# surficial_tilt_shield.net
KiCad netlist of a schematic drawn in EAGLE
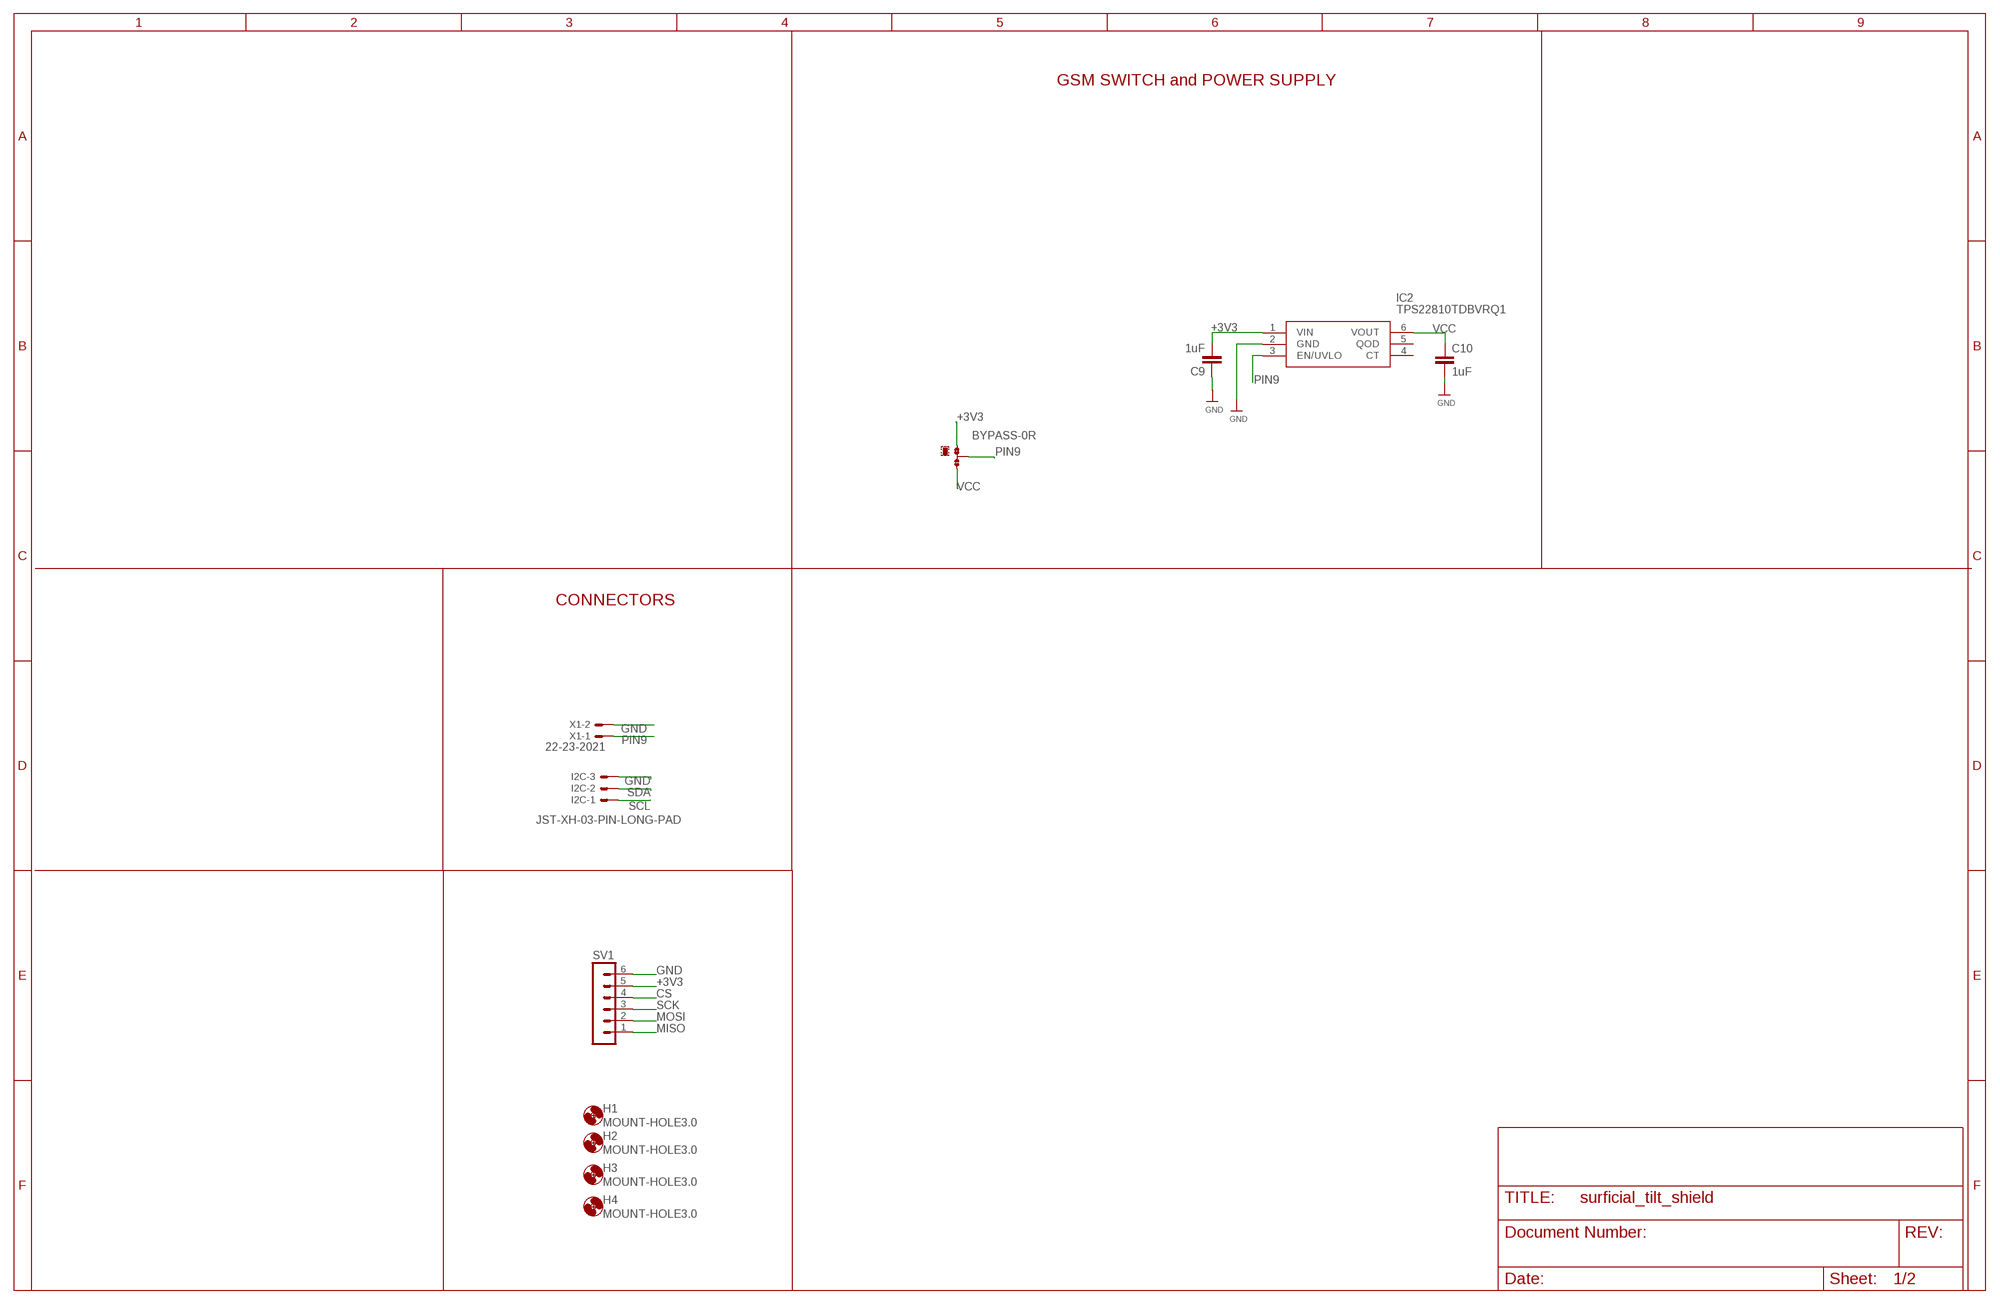
[diagram p0: schematic, sheet 1]
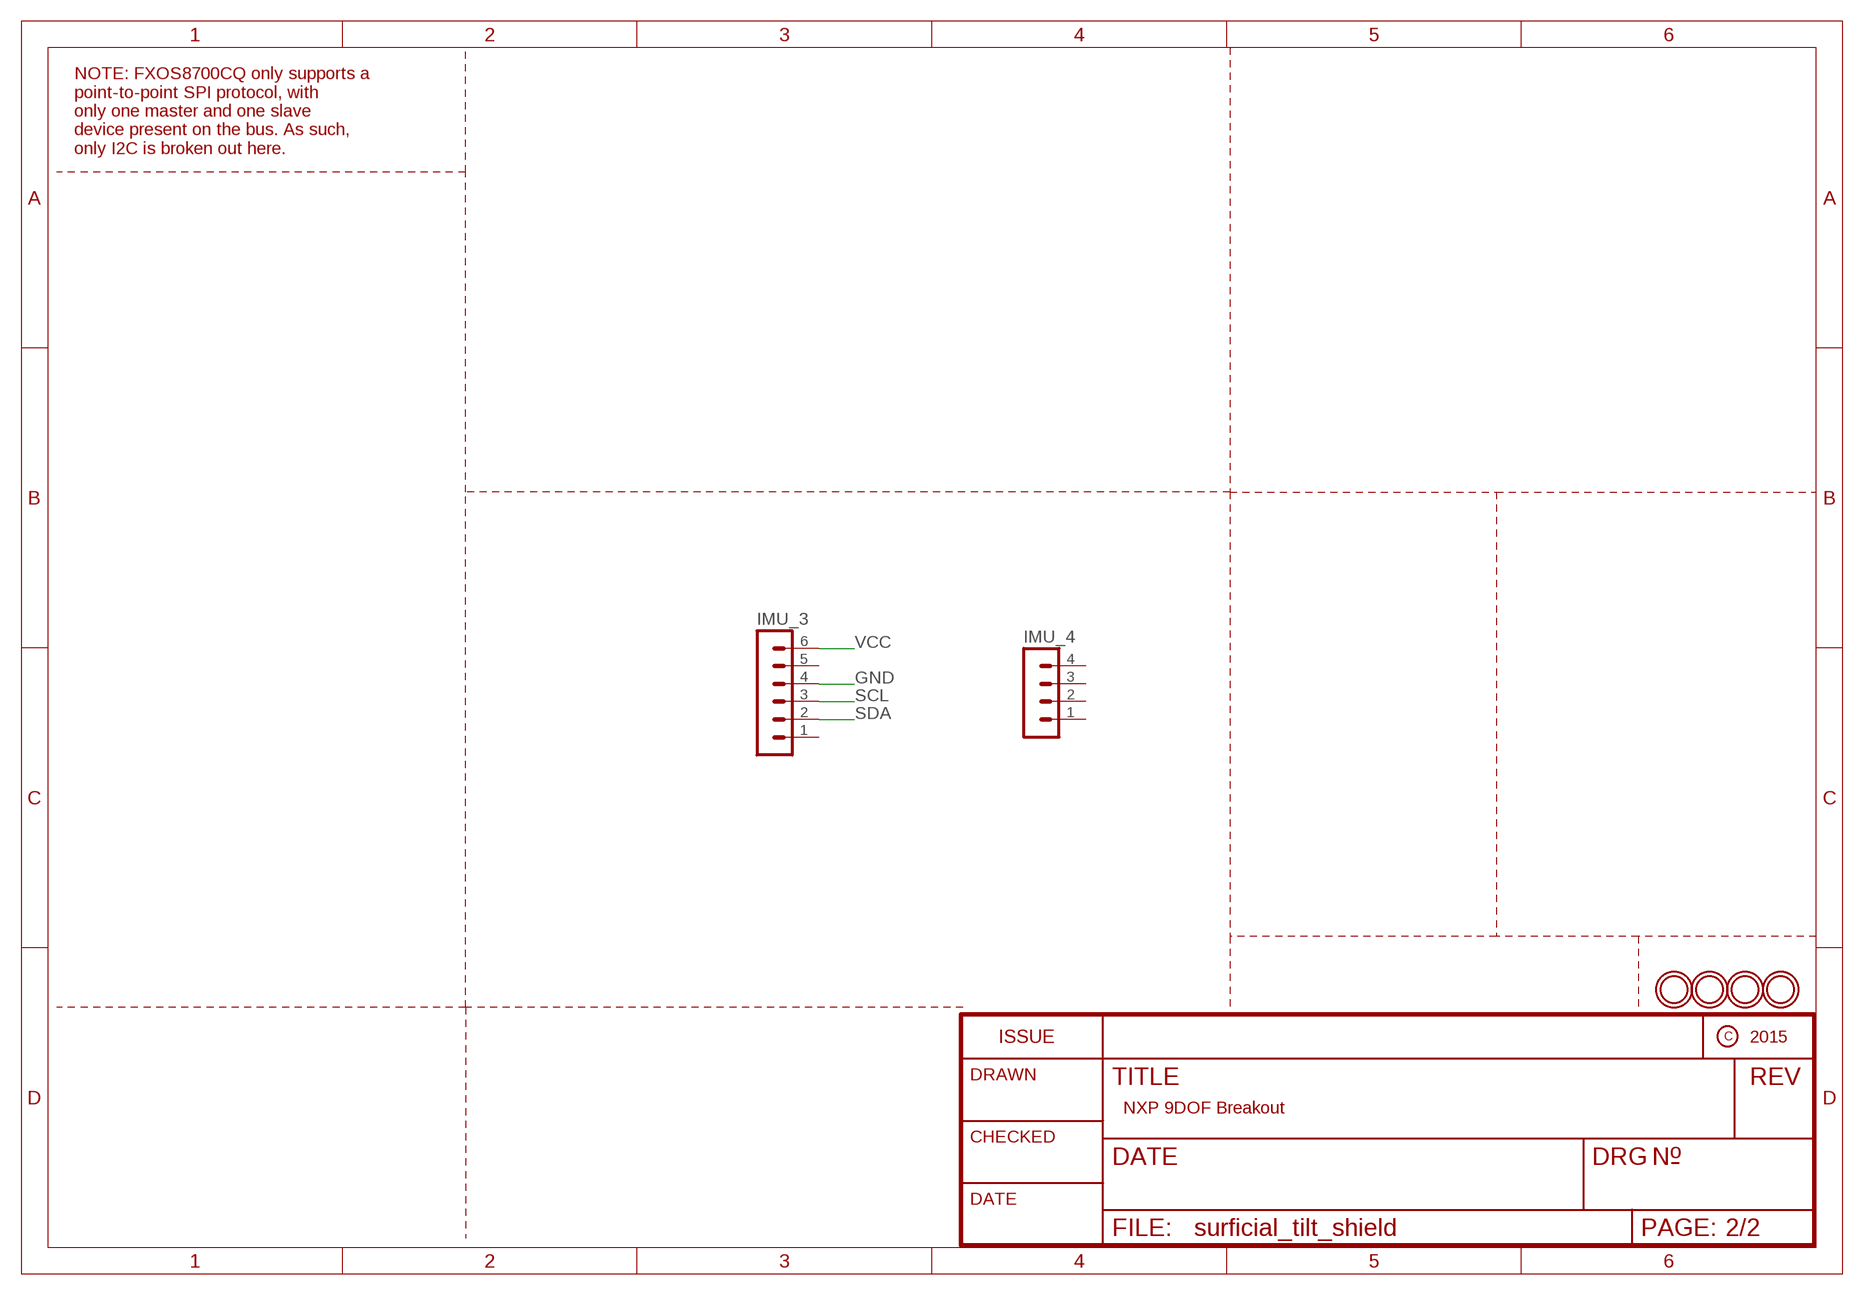
[diagram p1: schematic, sheet 2]

(export (version "E")
  (design (tool "Eeschema 10.0.6"))
  (components
    (comp (ref "BYPASS")
      (value "0R-JUMPB")
      (footprint "eagle-import:B0R-JMP")
      (libsource (lib "eagle-import") (part "0R-JUMPB"))
    )
    (comp (ref "C9")
      (value "1uF")
      (footprint "eagle-import:C0603")
      (libsource (lib "eagle-import") (part "CC0603"))
    )
    (comp (ref "C10")
      (value "1uF")
      (footprint "eagle-import:C0603")
      (libsource (lib "eagle-import") (part "CC0603"))
    )
    (comp (ref "H1")
      (value "MOUNT-HOLE3.0")
      (footprint "eagle-import:3,0")
      (libsource (lib "eagle-import") (part "MOUNT-HOLE3.0"))
    )
    (comp (ref "H2")
      (value "MOUNT-HOLE3.0")
      (footprint "eagle-import:3,0")
      (libsource (lib "eagle-import") (part "MOUNT-HOLE3.0"))
    )
    (comp (ref "H3")
      (value "MOUNT-HOLE3.0")
      (footprint "eagle-import:3,0")
      (libsource (lib "eagle-import") (part "MOUNT-HOLE3.0"))
    )
    (comp (ref "H4")
      (value "MOUNT-HOLE3.0")
      (footprint "eagle-import:3,0")
      (libsource (lib "eagle-import") (part "MOUNT-HOLE3.0"))
    )
    (comp (ref "I2C")
      (value "JST-XH-03-PIN-LONG-PAD")
      (footprint "eagle-import:JST-XH-03-PACKAGE-LONG-PAD")
      (libsource (lib "eagle-import") (part "JST-XH-03-PIN-LONG-PAD"))
    )
    (comp (ref "IC2")
      (value "TPS22810TDBVRQ1")
      (footprint "eagle-import:SOT95P280X145-6N")
      (libsource (lib "eagle-import") (part "TPS22810TDBVRQ1"))
    )
    (comp (ref "SV1")
      (value "MA06-1")
      (footprint "eagle-import:MA06-1")
      (libsource (lib "eagle-import") (part "MA06-1"))
    )
    (comp (ref "X1")
      (value "22-23-2021")
      (footprint "eagle-import:22-23-2021")
      (fields (field (name "MF") "MOLEX"))
      (libsource (lib "eagle-import") (part "22-23-2021"))
    )
    (comp (ref "IMU_3")
      (value "MA06-1")
      (footprint "eagle-import:MA06-1")
      (libsource (lib "eagle-import") (part "MA06-1"))
    )
    (comp (ref "IMU_4")
      (value "MA04-1")
      (footprint "eagle-import:MA04-1")
      (libsource (lib "eagle-import") (part "MA04-1"))
    )
    (comp (ref "U$1")
      (value "MOUNTINGHOLE2.5")
      (footprint "eagle-import:MOUNTINGHOLE_2.5_PLATED")
      (libsource (lib "eagle-import") (part "MOUNTINGHOLE2.5"))
    )
    (comp (ref "U$2")
      (value "MOUNTINGHOLE2.5")
      (footprint "eagle-import:MOUNTINGHOLE_2.5_PLATED")
      (libsource (lib "eagle-import") (part "MOUNTINGHOLE2.5"))
    )
    (comp (ref "U$3")
      (value "MOUNTINGHOLE2.5")
      (footprint "eagle-import:MOUNTINGHOLE_2.5_PLATED")
      (libsource (lib "eagle-import") (part "MOUNTINGHOLE2.5"))
    )
    (comp (ref "U$4")
      (value "MOUNTINGHOLE2.5")
      (footprint "eagle-import:MOUNTINGHOLE_2.5_PLATED")
      (libsource (lib "eagle-import") (part "MOUNTINGHOLE2.5"))
    )
  )
  (nets
    (net (code "1") (name "+3V3") (class "Default")
      (node (ref "BYPASS") (pin "1") (pinfunction "1_1") (pintype "passive"))
      (node (ref "C9") (pin "2") (pinfunction "2_2") (pintype "passive"))
      (node (ref "IC2") (pin "1") (pinfunction "VIN_1") (pintype "bidirectional"))
      (node (ref "SV1") (pin "5") (pinfunction "5_5") (pintype "passive"))
    )
    (net (code "2") (name "CS") (class "Default")
      (node (ref "SV1") (pin "4") (pinfunction "4_4") (pintype "passive"))
    )
    (net (code "3") (name "GND") (class "Default")
      (node (ref "C10") (pin "2") (pinfunction "2_2") (pintype "passive"))
      (node (ref "C9") (pin "1") (pinfunction "1_1") (pintype "passive"))
      (node (ref "I2C") (pin "3") (pinfunction "S_3") (pintype "passive"))
      (node (ref "IC2") (pin "2") (pinfunction "GND_2") (pintype "bidirectional"))
      (node (ref "IMU_3") (pin "4") (pinfunction "4_4") (pintype "passive"))
      (node (ref "SV1") (pin "6") (pinfunction "6_6") (pintype "passive"))
      (node (ref "X1") (pin "2") (pinfunction "S_2") (pintype "passive"))
    )
    (net (code "4") (name "MISO") (class "Default")
      (node (ref "SV1") (pin "1") (pinfunction "1_1") (pintype "passive"))
    )
    (net (code "5") (name "MOSI") (class "Default")
      (node (ref "SV1") (pin "2") (pinfunction "2_2") (pintype "passive"))
    )
    (net (code "6") (name "PIN9") (class "Default")
      (node (ref "BYPASS") (pin "2") (pinfunction "2_2") (pintype "passive"))
      (node (ref "IC2") (pin "3") (pinfunction "EN/UVLO_3") (pintype "bidirectional"))
      (node (ref "X1") (pin "1") (pinfunction "S_1") (pintype "passive"))
    )
    (net (code "7") (name "SCK") (class "Default")
      (node (ref "SV1") (pin "3") (pinfunction "3_3") (pintype "passive"))
    )
    (net (code "8") (name "SCL") (class "Default")
      (node (ref "I2C") (pin "1") (pinfunction "S_1") (pintype "passive"))
      (node (ref "IMU_3") (pin "3") (pinfunction "3_3") (pintype "passive"))
    )
    (net (code "9") (name "SDA") (class "Default")
      (node (ref "I2C") (pin "2") (pinfunction "S_2") (pintype "passive"))
      (node (ref "IMU_3") (pin "2") (pinfunction "2_2") (pintype "passive"))
    )
    (net (code "10") (name "VCC") (class "Default")
      (node (ref "BYPASS") (pin "3") (pinfunction "3_3") (pintype "passive"))
      (node (ref "C10") (pin "1") (pinfunction "1_1") (pintype "passive"))
      (node (ref "IC2") (pin "6") (pinfunction "VOUT_6") (pintype "bidirectional"))
      (node (ref "IMU_3") (pin "6") (pinfunction "6_6") (pintype "passive"))
    )
    (net (code "11") (name "unconnected-(IC2-CT-Pad4)") (class "Default")
      (node (ref "IC2") (pin "4") (pinfunction "CT_4") (pintype "bidirectional"))
    )
    (net (code "12") (name "unconnected-(IC2-QOD-Pad5)") (class "Default")
      (node (ref "IC2") (pin "5") (pinfunction "QOD_5") (pintype "bidirectional"))
    )
    (net (code "13") (name "unconnected-(IMU_3-Pad1)") (class "Default")
      (node (ref "IMU_3") (pin "1") (pinfunction "1_1") (pintype "passive"))
    )
    (net (code "14") (name "unconnected-(IMU_3-Pad5)") (class "Default")
      (node (ref "IMU_3") (pin "5") (pinfunction "5_5") (pintype "passive"))
    )
    (net (code "15") (name "unconnected-(IMU_4-Pad1)") (class "Default")
      (node (ref "IMU_4") (pin "1") (pinfunction "1_1") (pintype "passive"))
    )
    (net (code "16") (name "unconnected-(IMU_4-Pad2)") (class "Default")
      (node (ref "IMU_4") (pin "2") (pinfunction "2_2") (pintype "passive"))
    )
    (net (code "17") (name "unconnected-(IMU_4-Pad3)") (class "Default")
      (node (ref "IMU_4") (pin "3") (pinfunction "3_3") (pintype "passive"))
    )
    (net (code "18") (name "unconnected-(IMU_4-Pad4)") (class "Default")
      (node (ref "IMU_4") (pin "4") (pinfunction "4_4") (pintype "passive"))
    )
  )
)
